# Ocreeb_MK_2__combo_half__schematic.net
KiCad netlist of a schematic drawn in EAGLE
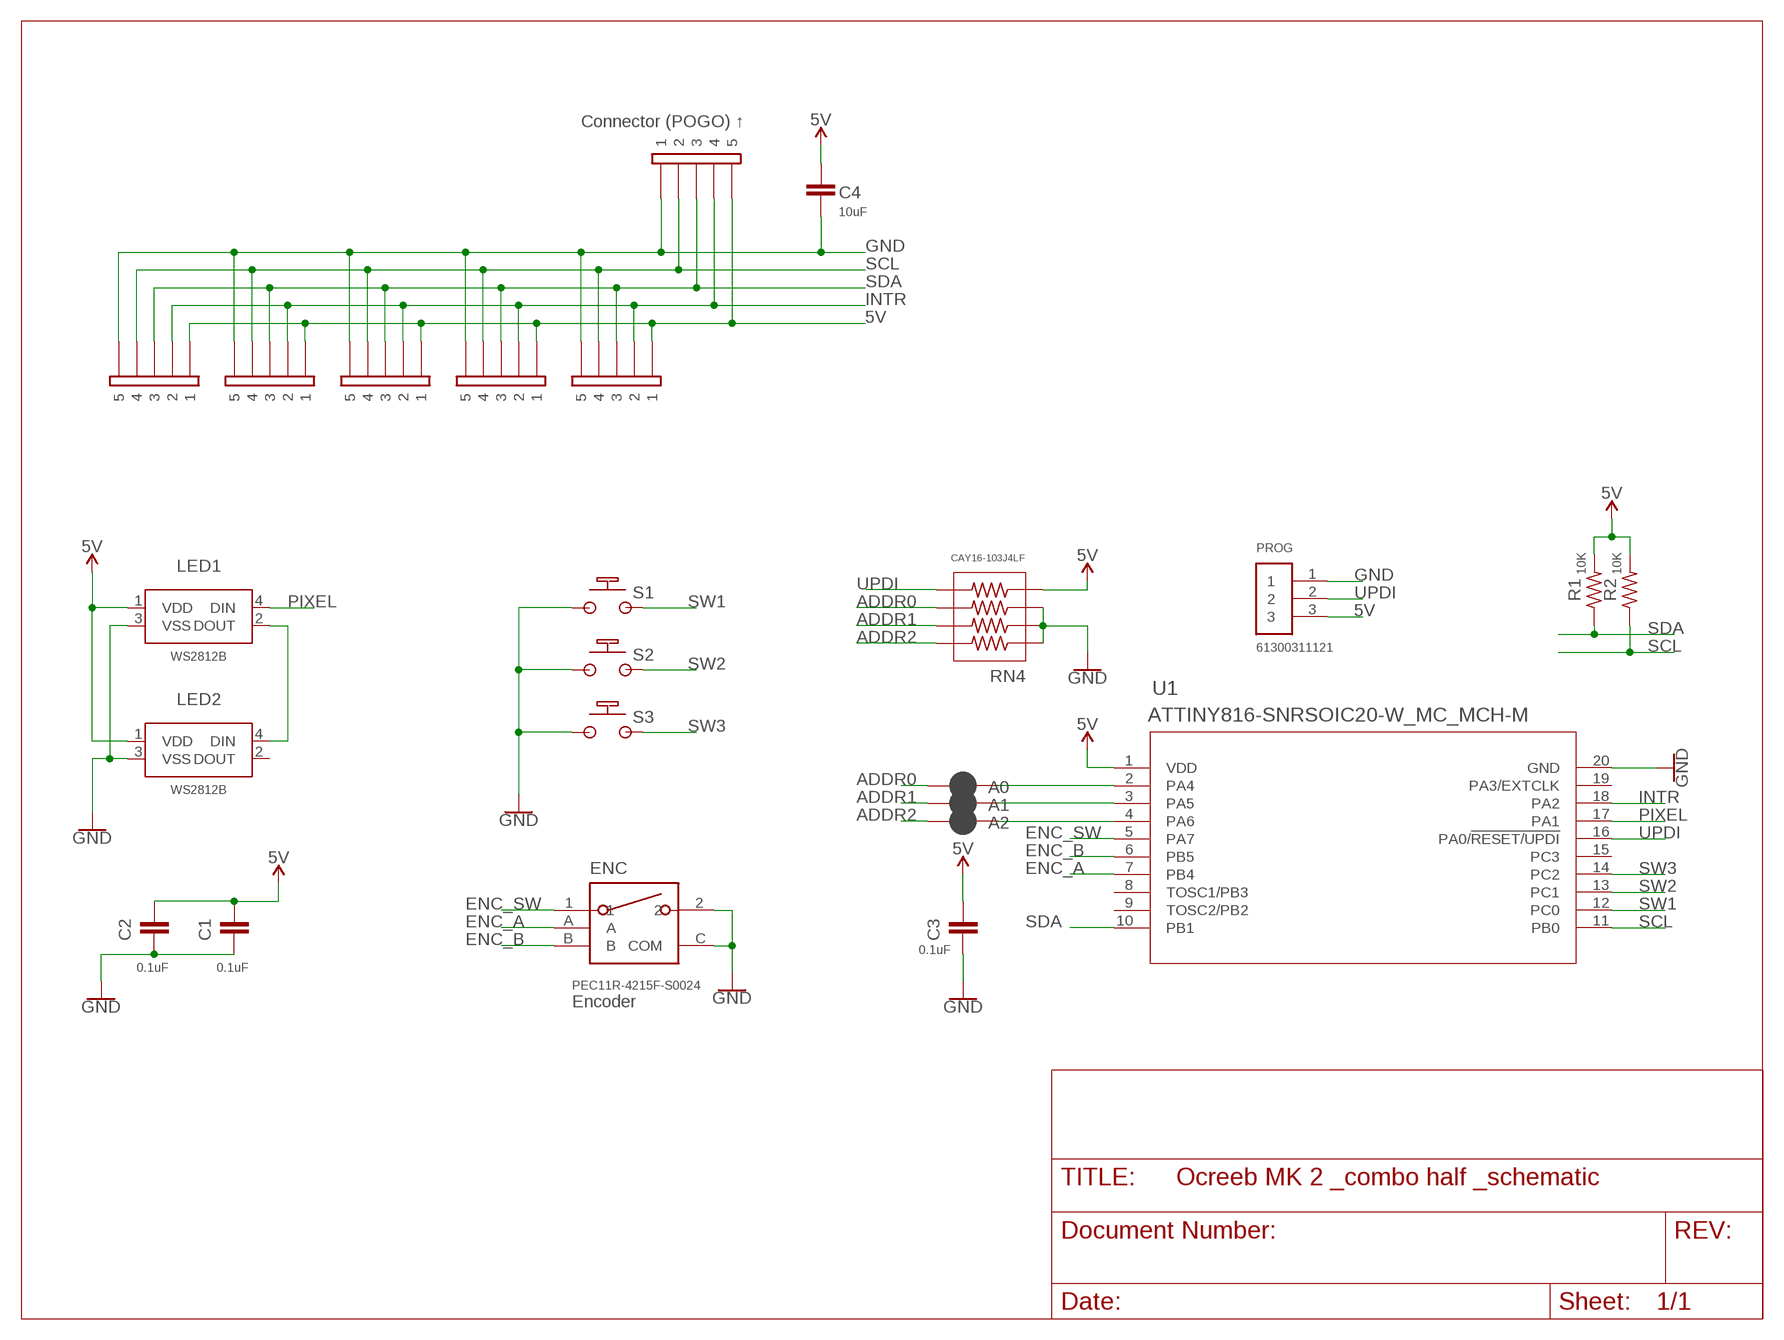
[diagram p0: schematic, sheet 1]

(export (version "E")
  (design (tool "Eeschema 10.0.6"))
  (components
    (comp (ref "A0")
      (value "JUMPER-SMT_2_NC_PASTE_SILK")
      (footprint "eagle-import:SMT-JUMPER_2_NC_PASTE_SILK")
      (libsource (lib "eagle-import") (part "JUMPER-SMT_2_NC_PASTE_SILK"))
    )
    (comp (ref "A1")
      (value "JUMPER-SMT_2_NC_PASTE_SILK")
      (footprint "eagle-import:SMT-JUMPER_2_NC_PASTE_SILK")
      (libsource (lib "eagle-import") (part "JUMPER-SMT_2_NC_PASTE_SILK"))
    )
    (comp (ref "A2")
      (value "JUMPER-SMT_2_NC_PASTE_SILK")
      (footprint "eagle-import:SMT-JUMPER_2_NC_PASTE_SILK")
      (libsource (lib "eagle-import") (part "JUMPER-SMT_2_NC_PASTE_SILK"))
    )
    (comp (ref "C1")
      (value "0.1uF")
      (footprint "eagle-import:CAPC1608X85")
      (libsource (lib "eagle-import") (part "CCHIP-0603(1608-METRIC)_"))
    )
    (comp (ref "C2")
      (value "0.1uF")
      (footprint "eagle-import:CAPC1608X85")
      (libsource (lib "eagle-import") (part "CCHIP-0603(1608-METRIC)_"))
    )
    (comp (ref "C3")
      (value "0.1uF")
      (footprint "eagle-import:CAPC1608X85")
      (libsource (lib "eagle-import") (part "CCHIP-0603(1608-METRIC)_"))
    )
    (comp (ref "C4")
      (value "10uF")
      (footprint "eagle-import:CAPC2012X110")
      (libsource (lib "eagle-import") (part "CCHIP-0805(2012-METRIC)_"))
    )
    (comp (ref "ENC")
      (value "PEC11R-4215F-S0024")
      (footprint "eagle-import:PEC11R-4215F-S0024")
      (fields
        (field (name "DIGIKEY_PART_NUMBER") "PEC11R-4215F-S0024-ND")
        (field (name "MANUFACTURER") "Bourns Inc.")
        (field (name "CREATED_BY") "PCBLayout.com")
      )
      (libsource (lib "eagle-import") (part "PEC11R-4215F-S0024"))
    )
    (comp (ref "LED1")
      (value "WS2812B")
      (footprint "eagle-import:WS2812B")
      (fields (field (name "MANUFACTURER") "Worldsemi"))
      (libsource (lib "eagle-import") (part "WS2812B"))
    )
    (comp (ref "LED2")
      (value "WS2812B")
      (footprint "eagle-import:WS2812B")
      (fields (field (name "MANUFACTURER") "Worldsemi"))
      (libsource (lib "eagle-import") (part "WS2812B"))
    )
    (comp (ref "PROG")
      (value "61300311121")
      (footprint "eagle-import:61300311121")
      (fields
        (field (name "DIGI_KEY_PART_NUMBER") "732-5316-ND")
        (field (name "MANUFACTURER") "Wurth Electronics Inc.")
        (field (name "CREATED_BY") "PCBLayout.com")
      )
      (libsource (lib "eagle-import") (part "61300311121"))
    )
    (comp (ref "R1")
      (value "10K")
      (footprint "eagle-import:RESC1608X60")
      (libsource (lib "eagle-import") (part "R-USCHIP-0603(1608-METRIC)_"))
    )
    (comp (ref "R2")
      (value "10K")
      (footprint "eagle-import:RESC1608X60")
      (libsource (lib "eagle-import") (part "R-USCHIP-0603(1608-METRIC)_"))
    )
    (comp (ref "RN4")
      (value "CAY16-103J4LF")
      (footprint "eagle-import:RESCAF80P320X160X60-8N")
      (fields (field (name "DIGIKEY_PART_NUMBER") "CAY16-103J4LFTR-ND") (field (name "MF") "Bourns"))
      (libsource (lib "eagle-import") (part "CAY16-103J4LF"))
    )
    (comp (ref "S1")
      (value "MX1A-11NNCHERRY_MX_SOLDER")
      (footprint "eagle-import:CHERRY_MX1A-11NN_SWITCH_NO_HOTSWAP")
      (libsource (lib "eagle-import") (part "MX1A-11NNCHERRY_MX_SOLDER"))
    )
    (comp (ref "S2")
      (value "MX1A-11NNCHERRY_MX_SOLDER")
      (footprint "eagle-import:CHERRY_MX1A-11NN_SWITCH_NO_HOTSWAP")
      (libsource (lib "eagle-import") (part "MX1A-11NNCHERRY_MX_SOLDER"))
    )
    (comp (ref "S3")
      (value "MX1A-11NNCHERRY_MX_SOLDER")
      (footprint "eagle-import:CHERRY_MX1A-11NN_SWITCH_NO_HOTSWAP")
      (libsource (lib "eagle-import") (part "MX1A-11NNCHERRY_MX_SOLDER"))
    )
    (comp (ref "U$1")
      (value "5PIN_EDGE5_POGO_EDGE_OUT_")
      (footprint "eagle-import:5_POGO_EDGE")
      (libsource (lib "eagle-import") (part "5PIN_EDGE5_POGO_EDGE_OUT_"))
    )
    (comp (ref "U$2")
      (value "5PIN_EDGE")
      (footprint "eagle-import:5_POGO_EDGE")
      (libsource (lib "eagle-import") (part "5PIN_EDGE"))
    )
    (comp (ref "U$3")
      (value "5PIN_EDGE")
      (footprint "eagle-import:5_POGO_EDGE")
      (libsource (lib "eagle-import") (part "5PIN_EDGE"))
    )
    (comp (ref "U$4")
      (value "5PIN_EDGE")
      (footprint "eagle-import:5_POGO_EDGE")
      (libsource (lib "eagle-import") (part "5PIN_EDGE"))
    )
    (comp (ref "U$5")
      (value "5PIN_EDGE")
      (footprint "eagle-import:5_POGO_EDGE")
      (libsource (lib "eagle-import") (part "5PIN_EDGE"))
    )
    (comp (ref "U$6")
      (value "5PIN_EDGE")
      (footprint "eagle-import:5_POGO_EDGE")
      (libsource (lib "eagle-import") (part "5PIN_EDGE"))
    )
    (comp (ref "U1")
      (value "ATTINY816-SNRSOIC20-W_MC_MCH-M")
      (footprint "eagle-import:SOIC20-W_MC_MCH-M")
      (fields
        (field (name "MANUFACTURER_PART_NUMBER") "ATTINY816-SNR")
        (field (name "COPYRIGHT") "Copyright (C) 2023 Ultra Librarian. All rights reserved.")
      )
      (libsource (lib "eagle-import") (part "ATTINY816-SNRSOIC20-W_MC_MCH-M"))
    )
  )
  (nets
    (net (code "1") (name "/ADDR0") (class "Default")
      (node (ref "A0") (pin "1") (pinfunction "1_1") (pintype "passive"))
      (node (ref "RN4") (pin "6") (pinfunction "6_6") (pintype "passive"))
    )
    (net (code "2") (name "/ADDR1") (class "Default")
      (node (ref "A1") (pin "1") (pinfunction "1_1") (pintype "passive"))
      (node (ref "RN4") (pin "7") (pinfunction "7_7") (pintype "passive"))
    )
    (net (code "3") (name "/ADDR2") (class "Default")
      (node (ref "A2") (pin "1") (pinfunction "1_1") (pintype "passive"))
      (node (ref "RN4") (pin "8") (pinfunction "8_8") (pintype "passive"))
    )
    (net (code "4") (name "/ENC_A") (class "Default")
      (node (ref "ENC") (pin "A") (pinfunction "A_A") (pintype "passive"))
      (node (ref "U1") (pin "7") (pinfunction "PB4_7") (pintype "bidirectional"))
    )
    (net (code "5") (name "/ENC_B") (class "Default")
      (node (ref "ENC") (pin "B") (pinfunction "B_B") (pintype "passive"))
      (node (ref "U1") (pin "6") (pinfunction "PB5_6") (pintype "bidirectional"))
    )
    (net (code "6") (name "/ENC_SW") (class "Default")
      (node (ref "ENC") (pin "1") (pinfunction "1_1") (pintype "passive"))
      (node (ref "U1") (pin "5") (pinfunction "PA7_5") (pintype "bidirectional"))
    )
    (net (code "7") (name "/INTR") (class "Default")
      (node (ref "U$1") (pin "4") (pinfunction "4_4") (pintype "bidirectional"))
      (node (ref "U$2") (pin "2") (pinfunction "2_2") (pintype "bidirectional"))
      (node (ref "U$3") (pin "2") (pinfunction "2_2") (pintype "bidirectional"))
      (node (ref "U$4") (pin "2") (pinfunction "2_2") (pintype "bidirectional"))
      (node (ref "U$5") (pin "2") (pinfunction "2_2") (pintype "bidirectional"))
      (node (ref "U$6") (pin "2") (pinfunction "2_2") (pintype "bidirectional"))
      (node (ref "U1") (pin "18") (pinfunction "PA2_18") (pintype "bidirectional"))
    )
    (net (code "8") (name "/PIXEL") (class "Default")
      (node (ref "LED1") (pin "4") (pinfunction "DIN_4") (pintype "input"))
      (node (ref "U1") (pin "17") (pinfunction "PA1_17") (pintype "bidirectional"))
    )
    (net (code "9") (name "/SCL") (class "Default")
      (node (ref "R2") (pin "1") (pinfunction "1_1") (pintype "passive"))
      (node (ref "U$1") (pin "2") (pinfunction "2_2") (pintype "bidirectional"))
      (node (ref "U$2") (pin "4") (pinfunction "4_4") (pintype "bidirectional"))
      (node (ref "U$3") (pin "4") (pinfunction "4_4") (pintype "bidirectional"))
      (node (ref "U$4") (pin "4") (pinfunction "4_4") (pintype "bidirectional"))
      (node (ref "U$5") (pin "4") (pinfunction "4_4") (pintype "bidirectional"))
      (node (ref "U$6") (pin "4") (pinfunction "4_4") (pintype "bidirectional"))
      (node (ref "U1") (pin "11") (pinfunction "PB0_11") (pintype "bidirectional"))
    )
    (net (code "10") (name "/SDA") (class "Default")
      (node (ref "R1") (pin "1") (pinfunction "1_1") (pintype "passive"))
      (node (ref "U$1") (pin "3") (pinfunction "3_3") (pintype "bidirectional"))
      (node (ref "U$2") (pin "3") (pinfunction "3_3") (pintype "bidirectional"))
      (node (ref "U$3") (pin "3") (pinfunction "3_3") (pintype "bidirectional"))
      (node (ref "U$4") (pin "3") (pinfunction "3_3") (pintype "bidirectional"))
      (node (ref "U$5") (pin "3") (pinfunction "3_3") (pintype "bidirectional"))
      (node (ref "U$6") (pin "3") (pinfunction "3_3") (pintype "bidirectional"))
      (node (ref "U1") (pin "10") (pinfunction "PB1_10") (pintype "bidirectional"))
    )
    (net (code "11") (name "/SW1") (class "Default")
      (node (ref "S1") (pin "2_ALT") (pinfunction "2_2_ALT") (pintype "passive"))
      (node (ref "U1") (pin "12") (pinfunction "PC0_12") (pintype "bidirectional"))
    )
    (net (code "12") (name "/SW2") (class "Default")
      (node (ref "S2") (pin "2_ALT") (pinfunction "2_2_ALT") (pintype "passive"))
      (node (ref "U1") (pin "13") (pinfunction "PC1_13") (pintype "bidirectional"))
    )
    (net (code "13") (name "/SW3") (class "Default")
      (node (ref "S3") (pin "2_ALT") (pinfunction "2_2_ALT") (pintype "passive"))
      (node (ref "U1") (pin "14") (pinfunction "PC2_14") (pintype "bidirectional"))
    )
    (net (code "14") (name "/UPDI") (class "Default")
      (node (ref "PROG") (pin "2") (pinfunction "2_2") (pintype "passive"))
      (node (ref "RN4") (pin "5") (pinfunction "5_5") (pintype "passive"))
      (node (ref "U1") (pin "16") (pinfunction "PA0/~{RESET/UPDI}_16") (pintype "bidirectional"))
    )
    (net (code "15") (name "5V") (class "Default")
      (node (ref "C1") (pin "2") (pinfunction "2_2") (pintype "passive"))
      (node (ref "C2") (pin "2") (pinfunction "2_2") (pintype "passive"))
      (node (ref "C3") (pin "2") (pinfunction "2_2") (pintype "passive"))
      (node (ref "C4") (pin "2") (pinfunction "2_2") (pintype "passive"))
      (node (ref "LED1") (pin "1") (pinfunction "VDD_1") (pintype "power_in"))
      (node (ref "LED2") (pin "1") (pinfunction "VDD_1") (pintype "power_in"))
      (node (ref "PROG") (pin "3") (pinfunction "3_3") (pintype "passive"))
      (node (ref "R1") (pin "2") (pinfunction "2_2") (pintype "passive"))
      (node (ref "R2") (pin "2") (pinfunction "2_2") (pintype "passive"))
      (node (ref "RN4") (pin "4") (pinfunction "4_4") (pintype "passive"))
      (node (ref "U$1") (pin "5") (pinfunction "5_5") (pintype "bidirectional"))
      (node (ref "U$2") (pin "1") (pinfunction "1_1") (pintype "bidirectional"))
      (node (ref "U$3") (pin "1") (pinfunction "1_1") (pintype "bidirectional"))
      (node (ref "U$4") (pin "1") (pinfunction "1_1") (pintype "bidirectional"))
      (node (ref "U$5") (pin "1") (pinfunction "1_1") (pintype "bidirectional"))
      (node (ref "U$6") (pin "1") (pinfunction "1_1") (pintype "bidirectional"))
      (node (ref "U1") (pin "1") (pinfunction "VDD_1") (pintype "power_in"))
    )
    (net (code "16") (name "GND") (class "Default")
      (node (ref "C1") (pin "1") (pinfunction "1_1") (pintype "passive"))
      (node (ref "C2") (pin "1") (pinfunction "1_1") (pintype "passive"))
      (node (ref "C3") (pin "1") (pinfunction "1_1") (pintype "passive"))
      (node (ref "C4") (pin "1") (pinfunction "1_1") (pintype "passive"))
      (node (ref "ENC") (pin "2") (pinfunction "2_2") (pintype "passive"))
      (node (ref "ENC") (pin "C") (pinfunction "COM_C") (pintype "passive"))
      (node (ref "LED1") (pin "3") (pinfunction "VSS_3") (pintype "power_in"))
      (node (ref "LED2") (pin "3") (pinfunction "VSS_3") (pintype "power_in"))
      (node (ref "PROG") (pin "1") (pinfunction "1_1") (pintype "passive"))
      (node (ref "RN4") (pin "1") (pinfunction "1_1") (pintype "passive"))
      (node (ref "RN4") (pin "2") (pinfunction "2_2") (pintype "passive"))
      (node (ref "RN4") (pin "3") (pinfunction "3_3") (pintype "passive"))
      (node (ref "S1") (pin "1_ALT") (pinfunction "1_1_ALT") (pintype "passive"))
      (node (ref "S2") (pin "1_ALT") (pinfunction "1_1_ALT") (pintype "passive"))
      (node (ref "S3") (pin "1_ALT") (pinfunction "1_1_ALT") (pintype "passive"))
      (node (ref "U$1") (pin "1") (pinfunction "1_1") (pintype "bidirectional"))
      (node (ref "U$2") (pin "5") (pinfunction "5_5") (pintype "bidirectional"))
      (node (ref "U$3") (pin "5") (pinfunction "5_5") (pintype "bidirectional"))
      (node (ref "U$4") (pin "5") (pinfunction "5_5") (pintype "bidirectional"))
      (node (ref "U$5") (pin "5") (pinfunction "5_5") (pintype "bidirectional"))
      (node (ref "U$6") (pin "5") (pinfunction "5_5") (pintype "bidirectional"))
      (node (ref "U1") (pin "20") (pinfunction "GND_20") (pintype "passive"))
    )
    (net (code "17") (name "Net-(LED1-DOUT)") (class "Default")
      (node (ref "LED1") (pin "2") (pinfunction "DOUT_2") (pintype "output"))
      (node (ref "LED2") (pin "4") (pinfunction "DIN_4") (pintype "input"))
    )
    (net (code "18") (name "Net-(U1-PA4)") (class "Default")
      (node (ref "A0") (pin "2") (pinfunction "2_2") (pintype "passive"))
      (node (ref "U1") (pin "2") (pinfunction "PA4_2") (pintype "bidirectional"))
    )
    (net (code "19") (name "Net-(U1-PA5)") (class "Default")
      (node (ref "A1") (pin "2") (pinfunction "2_2") (pintype "passive"))
      (node (ref "U1") (pin "3") (pinfunction "PA5_3") (pintype "bidirectional"))
    )
    (net (code "20") (name "Net-(U1-PA6)") (class "Default")
      (node (ref "A2") (pin "2") (pinfunction "2_2") (pintype "passive"))
      (node (ref "U1") (pin "4") (pinfunction "PA6_4") (pintype "bidirectional"))
    )
    (net (code "21") (name "unconnected-(LED2-DOUT-Pad2)") (class "Default")
      (node (ref "LED2") (pin "2") (pinfunction "DOUT_2") (pintype "output"))
    )
    (net (code "22") (name "unconnected-(U1-PA3{slash}EXTCLK-Pad19)") (class "Default")
      (node (ref "U1") (pin "19") (pinfunction "PA3/EXTCLK_19") (pintype "bidirectional"))
    )
    (net (code "23") (name "unconnected-(U1-PC3-Pad15)") (class "Default")
      (node (ref "U1") (pin "15") (pinfunction "PC3_15") (pintype "bidirectional"))
    )
    (net (code "24") (name "unconnected-(U1-TOSC1{slash}PB3-Pad8)") (class "Default")
      (node (ref "U1") (pin "8") (pinfunction "TOSC1/PB3_8") (pintype "bidirectional"))
    )
    (net (code "25") (name "unconnected-(U1-TOSC2{slash}PB2-Pad9)") (class "Default")
      (node (ref "U1") (pin "9") (pinfunction "TOSC2/PB2_9") (pintype "bidirectional"))
    )
  )
)
